# SparkFun_Bluetooth_Beacon_IN100.net
KiCad netlist of a schematic drawn in EAGLE
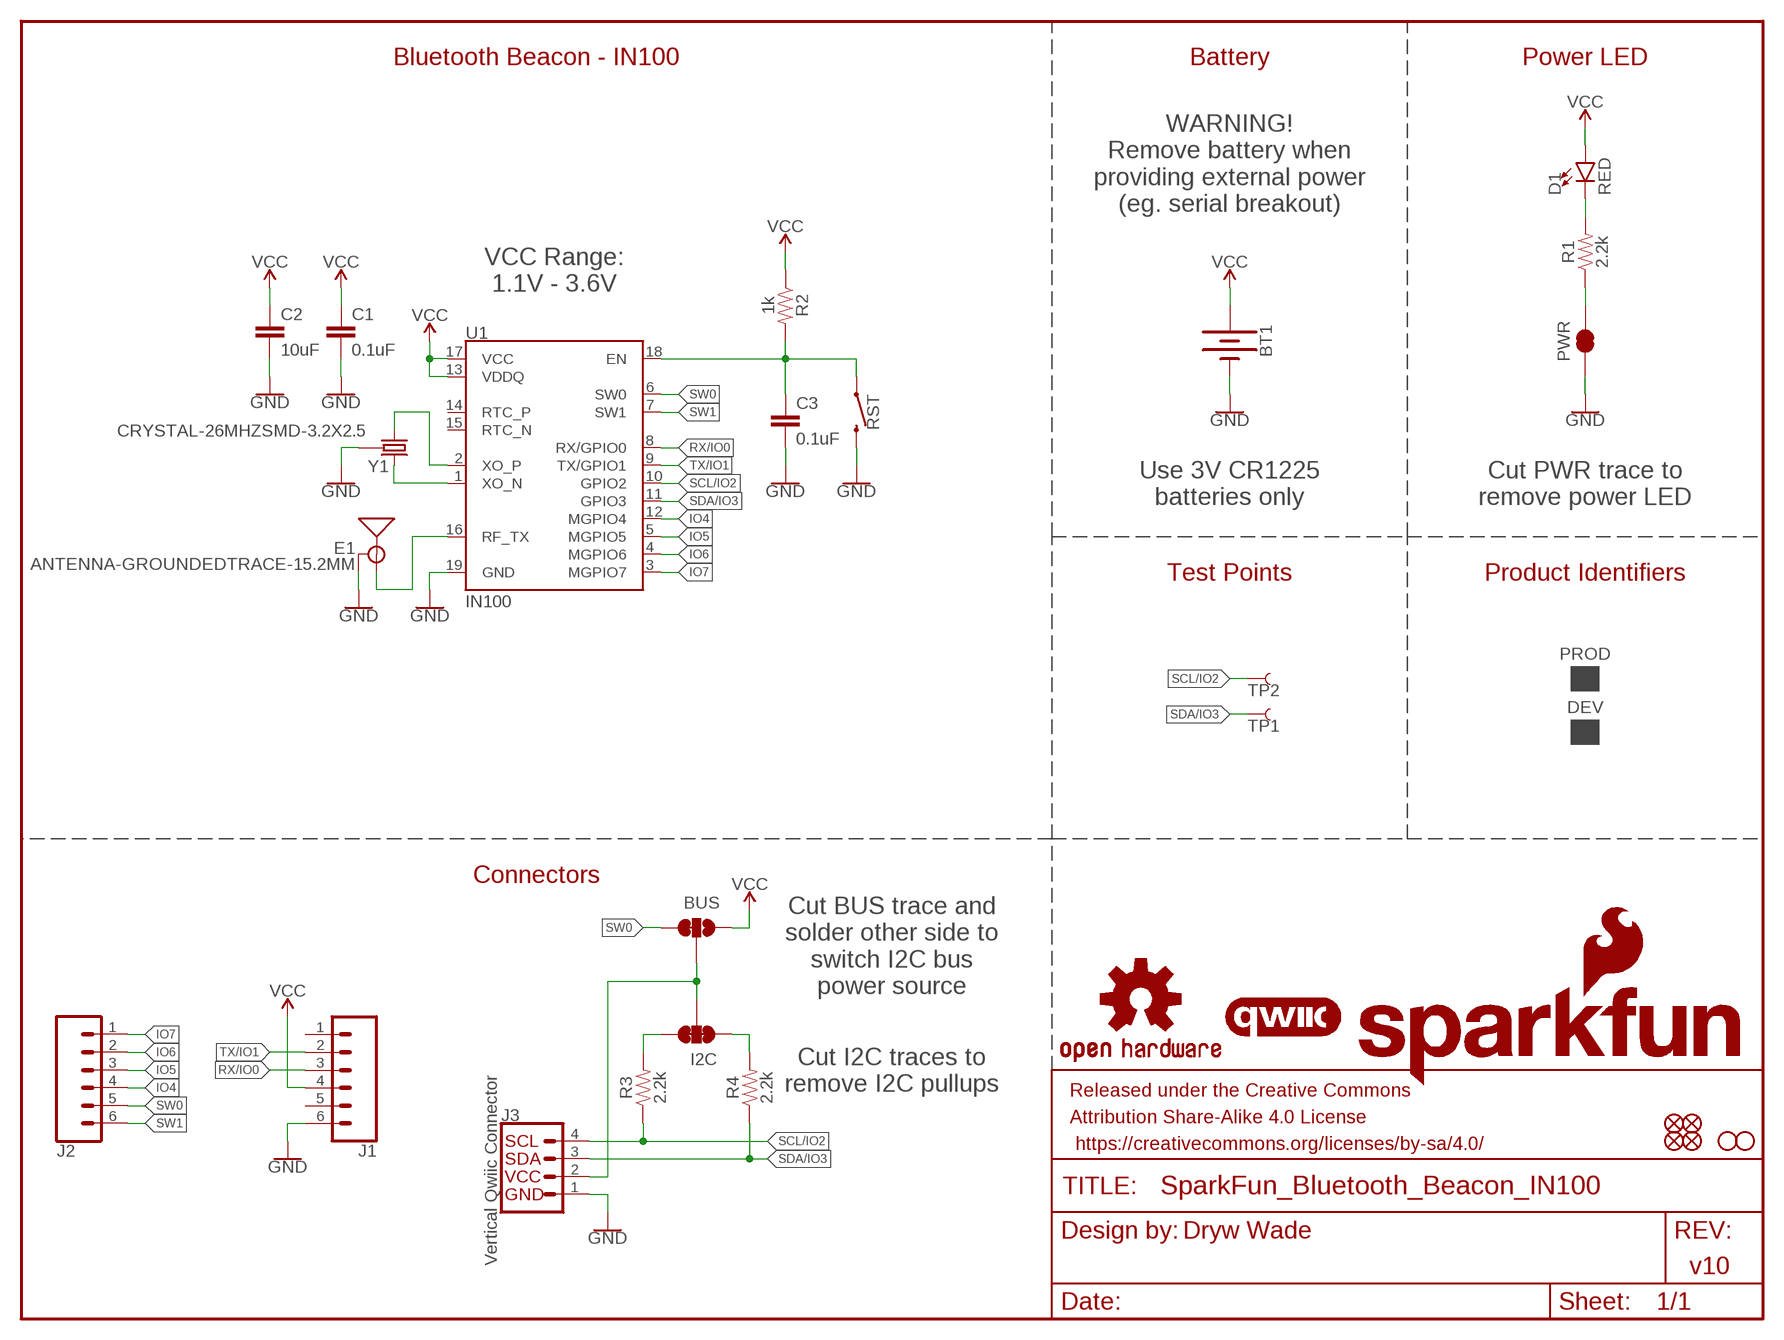
[diagram p0: schematic, sheet 1]

(export (version "E")
  (design (tool "Eeschema 10.0.6"))
  (components
    (comp (ref "BT1")
      (value "BATTERY-12MM_SMD")
      (footprint "eagle-import:BATTCON_12MM")
      (libsource (lib "eagle-import") (part "BATTERY-12MM_SMD"))
    )
    (comp (ref "BUS")
      (value "JUMPER-SMT_3_1-NC_TRACE_SILK")
      (footprint "eagle-import:SMT-JUMPER_3_1-NC_TRACE_SILK")
      (libsource (lib "eagle-import") (part "JUMPER-SMT_3_1-NC_TRACE_SILK"))
    )
    (comp (ref "C1")
      (value "0.1uF")
      (footprint "eagle-import:0402-TIGHT")
      (libsource (lib "eagle-import") (part "0.1UF-0402T-6.3V-10%-X7R"))
    )
    (comp (ref "C2")
      (value "10uF")
      (footprint "eagle-import:0402-TIGHT")
      (libsource (lib "eagle-import") (part "10UF-0402T-6.3V-20%"))
    )
    (comp (ref "C3")
      (value "0.1uF")
      (footprint "eagle-import:0402-TIGHT")
      (libsource (lib "eagle-import") (part "0.1UF-0402T-6.3V-10%-X7R"))
    )
    (comp (ref "D1")
      (value "RED")
      (footprint "eagle-import:LED-0402")
      (libsource (lib "eagle-import") (part "LED-RED_0402"))
    )
    (comp (ref "DEV")
      (value "PROD_ID_PASTE_SILK")
      (footprint "eagle-import:PRODUCT_IDENT_PASTE_SILK")
      (libsource (lib "eagle-import") (part "PROD_ID_PASTE_SILK"))
    )
    (comp (ref "E1")
      (value "ANTENNA-GROUNDEDTRACE-15.2MM")
      (footprint "eagle-import:TRACE_ANTENNA_2.4GHZ_15.2MM")
      (libsource (lib "eagle-import") (part "ANTENNA-GROUNDEDTRACE-15.2MM"))
    )
    (comp (ref "FD1")
      (value "FIDUCIAL1X2")
      (footprint "eagle-import:FIDUCIAL-1X2")
      (libsource (lib "eagle-import") (part "FIDUCIAL1X2"))
    )
    (comp (ref "FD2")
      (value "FIDUCIAL1X2")
      (footprint "eagle-import:FIDUCIAL-1X2")
      (libsource (lib "eagle-import") (part "FIDUCIAL1X2"))
    )
    (comp (ref "FD3")
      (value "FIDUCIAL1X2")
      (footprint "eagle-import:FIDUCIAL-1X2")
      (libsource (lib "eagle-import") (part "FIDUCIAL1X2"))
    )
    (comp (ref "FD4")
      (value "FIDUCIAL1X2")
      (footprint "eagle-import:FIDUCIAL-1X2")
      (libsource (lib "eagle-import") (part "FIDUCIAL1X2"))
    )
    (comp (ref "FRAME1")
      (value "FRAME-LETTER")
      (footprint "eagle-import:CREATIVE_COMMONS")
      (libsource (lib "eagle-import") (part "FRAME-LETTER"))
    )
    (comp (ref "H1")
      (value "STAND-OFF")
      (footprint "eagle-import:STAND-OFF")
      (libsource (lib "eagle-import") (part "STAND-OFF"))
    )
    (comp (ref "H2")
      (value "STAND-OFF")
      (footprint "eagle-import:STAND-OFF")
      (libsource (lib "eagle-import") (part "STAND-OFF"))
    )
    (comp (ref "I2C")
      (value "JUMPER-SMT_3_2-NC_TRACE_SILK")
      (footprint "eagle-import:SMT-JUMPER_3_2-NC_TRACE_SILK")
      (libsource (lib "eagle-import") (part "JUMPER-SMT_3_2-NC_TRACE_SILK"))
    )
    (comp (ref "J1")
      (value "CONN_06NO_SILK_NO_POP")
      (footprint "eagle-import:1X06_NO_SILK")
      (libsource (lib "eagle-import") (part "CONN_06NO_SILK_NO_POP"))
    )
    (comp (ref "J2")
      (value "CONN_06NO_SILK_NO_POP")
      (footprint "eagle-import:1X06_NO_SILK")
      (libsource (lib "eagle-import") (part "CONN_06NO_SILK_NO_POP"))
    )
    (comp (ref "J3")
      (value "Vertical Qwiic Connector")
      (footprint "eagle-import:JST04_1MM_VERT")
      (libsource (lib "eagle-import") (part "QWIIC_CONNECTOR"))
    )
    (comp (ref "LOGO1")
      (value "OSHW-LOGOS")
      (footprint "eagle-import:OSHW-LOGO-S")
      (libsource (lib "eagle-import") (part "OSHW-LOGOS"))
    )
    (comp (ref "LOGO2")
      (value "SFE_LOGO_NAME_FLAME.1_INCH")
      (footprint "eagle-import:SFE_LOGO_NAME_FLAME_.1")
      (libsource (lib "eagle-import") (part "SFE_LOGO_NAME_FLAME.1_INCH"))
    )
    (comp (ref "LOGO3")
      (value "QWIIC_LOGO_3MM")
      (footprint "eagle-import:QWIIC_3MM")
      (libsource (lib "eagle-import") (part "QWIIC_LOGO_3MM"))
    )
    (comp (ref "PROD")
      (value "PROD_ID_PASTE_SILK")
      (footprint "eagle-import:PRODUCT_IDENT_PASTE_SILK")
      (libsource (lib "eagle-import") (part "PROD_ID_PASTE_SILK"))
    )
    (comp (ref "PWR")
      (value "JUMPER-SMT_2_NC_TRACE_SILK")
      (footprint "eagle-import:SMT-JUMPER_2_NC_TRACE_SILK")
      (libsource (lib "eagle-import") (part "JUMPER-SMT_2_NC_TRACE_SILK"))
    )
    (comp (ref "R1")
      (value "2.2k")
      (footprint "eagle-import:0402-TIGHT")
      (libsource (lib "eagle-import") (part "2.2KOHM-0402T-1/16W-1%"))
    )
    (comp (ref "R2")
      (value "1k")
      (footprint "eagle-import:0402-TIGHT")
      (libsource (lib "eagle-import") (part "1KOHM-0402T-1/16W-1%"))
    )
    (comp (ref "R3")
      (value "2.2k")
      (footprint "eagle-import:0402-TIGHT")
      (libsource (lib "eagle-import") (part "2.2KOHM-0402T-1/16W-1%"))
    )
    (comp (ref "R4")
      (value "2.2k")
      (footprint "eagle-import:0402-TIGHT")
      (libsource (lib "eagle-import") (part "2.2KOHM-0402T-1/16W-1%"))
    )
    (comp (ref "RST")
      (value "MOMENTARY-SWITCH-SPST-SMD-4.6X2.8MM")
      (footprint "eagle-import:TACTILE_SWITCH_SMD_4.6X2.8MM")
      (libsource (lib "eagle-import") (part "MOMENTARY-SWITCH-SPST-SMD-4.6X2.8MM"))
    )
    (comp (ref "TP1")
      (value "TEST-POINT3")
      (footprint "eagle-import:PAD.03X.03")
      (libsource (lib "eagle-import") (part "TEST-POINT3"))
    )
    (comp (ref "TP2")
      (value "TEST-POINT3")
      (footprint "eagle-import:PAD.03X.03")
      (libsource (lib "eagle-import") (part "TEST-POINT3"))
    )
    (comp (ref "U1")
      (value "IN100")
      (footprint "eagle-import:IN100")
      (libsource (lib "eagle-import") (part "IN100"))
    )
    (comp (ref "Y1")
      (value "CRYSTAL-26MHZSMD-3.2X2.5")
      (footprint "eagle-import:CRYSTAL-SMD-3.2X2.5MM")
      (libsource (lib "eagle-import") (part "CRYSTAL-26MHZSMD-3.2X2.5"))
    )
  )
  (nets
    (net (code "1") (name "GND") (class "Default")
      (node (ref "BT1") (pin "GND") (pinfunction "-_GND") (pintype "power_in"))
      (node (ref "C1") (pin "2") (pinfunction "2_2") (pintype "passive"))
      (node (ref "C2") (pin "2") (pinfunction "2_2") (pintype "passive"))
      (node (ref "C3") (pin "2") (pinfunction "2_2") (pintype "passive"))
      (node (ref "E1") (pin "GND") (pinfunction "GND_GND") (pintype "bidirectional"))
      (node (ref "J1") (pin "6") (pinfunction "6_6") (pintype "passive"))
      (node (ref "J3") (pin "1") (pinfunction "1_1") (pintype "power_in"))
      (node (ref "PWR") (pin "1") (pinfunction "1_1") (pintype "passive"))
      (node (ref "RST") (pin "3") (pinfunction "2_3") (pintype "passive"))
      (node (ref "RST") (pin "4") (pinfunction "2_4") (pintype "passive"))
      (node (ref "U1") (pin "19") (pinfunction "GND_19") (pintype "power_in"))
      (node (ref "Y1") (pin "2") (pinfunction "GND_2") (pintype "power_in"))
      (node (ref "Y1") (pin "4") (pinfunction "GND_4") (pintype "power_in"))
    )
    (net (code "2") (name "IO4") (class "Default")
      (node (ref "J2") (pin "4") (pinfunction "4_4") (pintype "passive"))
      (node (ref "U1") (pin "12") (pinfunction "MGPIO4_12") (pintype "bidirectional"))
    )
    (net (code "3") (name "IO5") (class "Default")
      (node (ref "J2") (pin "3") (pinfunction "3_3") (pintype "passive"))
      (node (ref "U1") (pin "5") (pinfunction "MGPIO5_5") (pintype "bidirectional"))
    )
    (net (code "4") (name "IO6") (class "Default")
      (node (ref "J2") (pin "2") (pinfunction "2_2") (pintype "passive"))
      (node (ref "U1") (pin "4") (pinfunction "MGPIO6_4") (pintype "bidirectional"))
    )
    (net (code "5") (name "IO7") (class "Default")
      (node (ref "J2") (pin "1") (pinfunction "1_1") (pintype "passive"))
      (node (ref "U1") (pin "3") (pinfunction "MGPIO7_3") (pintype "bidirectional"))
    )
    (net (code "6") (name "Net-(BUS-Pad2)") (class "Default")
      (node (ref "BUS") (pin "2") (pinfunction "2_2") (pintype "passive"))
      (node (ref "I2C") (pin "2") (pinfunction "2_2") (pintype "passive"))
      (node (ref "J3") (pin "2") (pinfunction "2_2") (pintype "power_in"))
    )
    (net (code "7") (name "Net-(D1-PadC)") (class "Default")
      (node (ref "D1") (pin "C") (pinfunction "C_C") (pintype "passive"))
      (node (ref "R1") (pin "2") (pinfunction "2_2") (pintype "passive"))
    )
    (net (code "8") (name "Net-(E1-SIGNAL)") (class "Default")
      (node (ref "E1") (pin "ANT") (pinfunction "SIGNAL_ANT") (pintype "bidirectional"))
      (node (ref "U1") (pin "16") (pinfunction "RF_TX_16") (pintype "bidirectional"))
    )
    (net (code "9") (name "Net-(I2C-Pad1)") (class "Default")
      (node (ref "I2C") (pin "1") (pinfunction "1_1") (pintype "passive"))
      (node (ref "R4") (pin "2") (pinfunction "2_2") (pintype "passive"))
    )
    (net (code "10") (name "Net-(I2C-Pad3)") (class "Default")
      (node (ref "I2C") (pin "3") (pinfunction "3_3") (pintype "passive"))
      (node (ref "R3") (pin "2") (pinfunction "2_2") (pintype "passive"))
    )
    (net (code "11") (name "Net-(PWR-Pad2)") (class "Default")
      (node (ref "PWR") (pin "2") (pinfunction "2_2") (pintype "passive"))
      (node (ref "R1") (pin "1") (pinfunction "1_1") (pintype "passive"))
    )
    (net (code "12") (name "Net-(U1-EN)") (class "Default")
      (node (ref "C3") (pin "1") (pinfunction "1_1") (pintype "passive"))
      (node (ref "R2") (pin "2") (pinfunction "2_2") (pintype "passive"))
      (node (ref "RST") (pin "1") (pinfunction "1_1") (pintype "passive"))
      (node (ref "RST") (pin "2") (pinfunction "1_2") (pintype "passive"))
      (node (ref "U1") (pin "18") (pinfunction "EN_18") (pintype "input"))
    )
    (net (code "13") (name "Net-(U1-XO_N)") (class "Default")
      (node (ref "U1") (pin "1") (pinfunction "XO_N_1") (pintype "bidirectional"))
      (node (ref "Y1") (pin "3") (pinfunction "2_3") (pintype "passive"))
    )
    (net (code "14") (name "Net-(U1-XO_P)") (class "Default")
      (node (ref "U1") (pin "2") (pinfunction "XO_P_2") (pintype "bidirectional"))
      (node (ref "Y1") (pin "1") (pinfunction "1_1") (pintype "passive"))
    )
    (net (code "15") (name "RX{slash}IO0") (class "Default")
      (node (ref "J1") (pin "3") (pinfunction "3_3") (pintype "passive"))
      (node (ref "U1") (pin "8") (pinfunction "RX/GPIO0_8") (pintype "bidirectional"))
    )
    (net (code "16") (name "SCL{slash}IO2") (class "Default")
      (node (ref "J3") (pin "4") (pinfunction "4_4") (pintype "passive"))
      (node (ref "R3") (pin "1") (pinfunction "1_1") (pintype "passive"))
      (node (ref "TP2") (pin "1") (pinfunction "1_1") (pintype "bidirectional"))
      (node (ref "U1") (pin "10") (pinfunction "GPIO2_10") (pintype "bidirectional"))
    )
    (net (code "17") (name "SDA{slash}IO3") (class "Default")
      (node (ref "J3") (pin "3") (pinfunction "3_3") (pintype "passive"))
      (node (ref "R4") (pin "1") (pinfunction "1_1") (pintype "passive"))
      (node (ref "TP1") (pin "1") (pinfunction "1_1") (pintype "bidirectional"))
      (node (ref "U1") (pin "11") (pinfunction "GPIO3_11") (pintype "bidirectional"))
    )
    (net (code "18") (name "SW0") (class "Default")
      (node (ref "BUS") (pin "3") (pinfunction "3_3") (pintype "passive"))
      (node (ref "J2") (pin "5") (pinfunction "5_5") (pintype "passive"))
      (node (ref "U1") (pin "6") (pinfunction "SW0_6") (pintype "output"))
    )
    (net (code "19") (name "SW1") (class "Default")
      (node (ref "J2") (pin "6") (pinfunction "6_6") (pintype "passive"))
      (node (ref "U1") (pin "7") (pinfunction "SW1_7") (pintype "output"))
    )
    (net (code "20") (name "TX{slash}IO1") (class "Default")
      (node (ref "J1") (pin "2") (pinfunction "2_2") (pintype "passive"))
      (node (ref "U1") (pin "9") (pinfunction "TX/GPIO1_9") (pintype "bidirectional"))
    )
    (net (code "21") (name "VCC") (class "Default")
      (node (ref "BT1") (pin "PWR@1") (pinfunction "+_PWR@1") (pintype "power_in"))
      (node (ref "BT1") (pin "PWR@2") (pinfunction "+_PWR@2") (pintype "power_in"))
      (node (ref "BUS") (pin "1") (pinfunction "1_1") (pintype "passive"))
      (node (ref "C1") (pin "1") (pinfunction "1_1") (pintype "passive"))
      (node (ref "C2") (pin "1") (pinfunction "1_1") (pintype "passive"))
      (node (ref "D1") (pin "A") (pinfunction "A_A") (pintype "passive"))
      (node (ref "J1") (pin "4") (pinfunction "4_4") (pintype "passive"))
      (node (ref "R2") (pin "1") (pinfunction "1_1") (pintype "passive"))
      (node (ref "U1") (pin "13") (pinfunction "VDDQ_13") (pintype "power_in"))
      (node (ref "U1") (pin "17") (pinfunction "VCC_17") (pintype "power_in"))
    )
    (net (code "22") (name "unconnected-(J1-Pad1)") (class "Default")
      (node (ref "J1") (pin "1") (pinfunction "1_1") (pintype "passive"))
    )
    (net (code "23") (name "unconnected-(J1-Pad5)") (class "Default")
      (node (ref "J1") (pin "5") (pinfunction "5_5") (pintype "passive"))
    )
    (net (code "24") (name "unconnected-(U1-RTC_N-Pad15)") (class "Default")
      (node (ref "U1") (pin "15") (pinfunction "RTC_N_15") (pintype "bidirectional"))
    )
    (net (code "25") (name "unconnected-(U1-RTC_P-Pad14)") (class "Default")
      (node (ref "U1") (pin "14") (pinfunction "RTC_P_14") (pintype "bidirectional"))
    )
  )
)
